# tut1.net
KiCad netlist of a schematic drawn in EAGLE
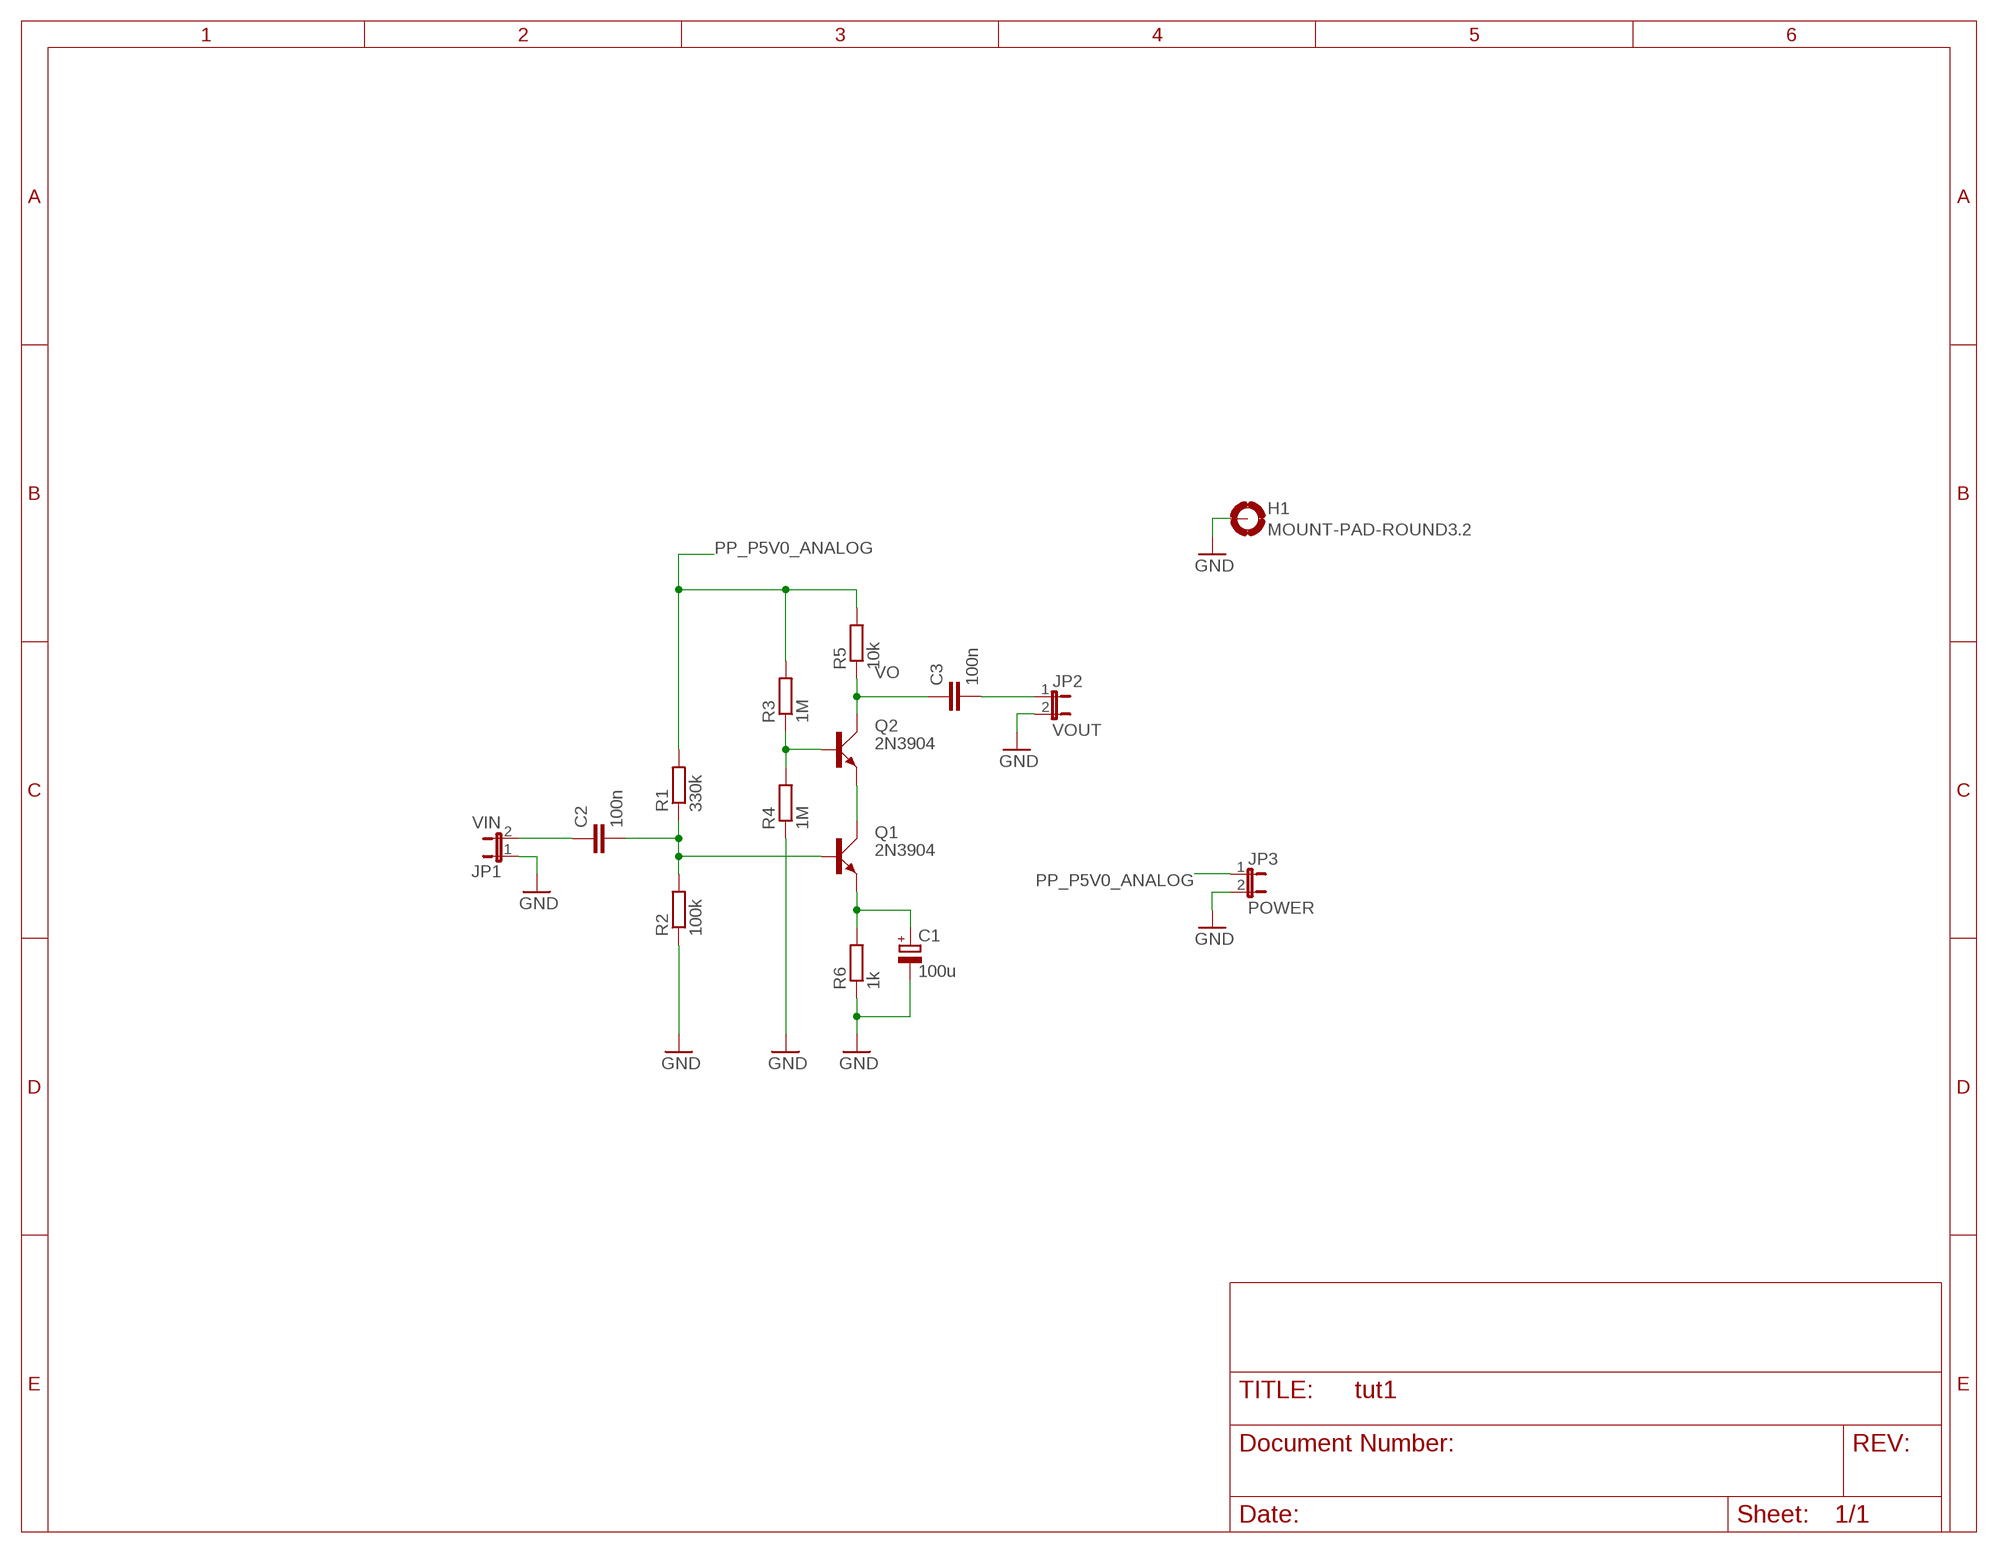
[diagram p0: schematic, sheet 1]

(export (version "E")
  (design (tool "Eeschema 10.0.6"))
  (components
    (comp (ref "C1")
      (value "100u")
      (footprint "eagle-import:E5-10,5")
      (libsource (lib "eagle-import") (part "CPOL-EUE5-10.5"))
    )
    (comp (ref "C2")
      (value "100n")
      (footprint "eagle-import:C050-025X075")
      (libsource (lib "eagle-import") (part "C-EU050-025X075"))
    )
    (comp (ref "C3")
      (value "100n")
      (footprint "eagle-import:C050-025X075")
      (libsource (lib "eagle-import") (part "C-EU050-025X075"))
    )
    (comp (ref "H1")
      (value "MOUNT-PAD-ROUND3.2")
      (footprint "eagle-import:3,2-PAD")
      (libsource (lib "eagle-import") (part "MOUNT-PAD-ROUND3.2"))
    )
    (comp (ref "JP1")
      (value "VIN")
      (footprint "eagle-import:JP1")
      (libsource (lib "eagle-import") (part "JP1E"))
    )
    (comp (ref "JP2")
      (value "VOUT")
      (footprint "eagle-import:JP1")
      (libsource (lib "eagle-import") (part "JP1E"))
    )
    (comp (ref "JP3")
      (value "POWER")
      (footprint "eagle-import:JP1")
      (libsource (lib "eagle-import") (part "JP1E"))
    )
    (comp (ref "Q1")
      (value "2N3904")
      (footprint "eagle-import:TO92D")
      (libsource (lib "eagle-import") (part "2N3904"))
    )
    (comp (ref "Q2")
      (value "2N3904")
      (footprint "eagle-import:TO92D")
      (libsource (lib "eagle-import") (part "2N3904"))
    )
    (comp (ref "R1")
      (value "330k")
      (footprint "eagle-import:0207_10")
      (libsource (lib "eagle-import") (part "R-EU_0207/10"))
    )
    (comp (ref "R2")
      (value "100k")
      (footprint "eagle-import:0207_10")
      (libsource (lib "eagle-import") (part "R-EU_0207/10"))
    )
    (comp (ref "R3")
      (value "1M")
      (footprint "eagle-import:0207_10")
      (libsource (lib "eagle-import") (part "R-EU_0207/10"))
    )
    (comp (ref "R4")
      (value "1M")
      (footprint "eagle-import:0207_10")
      (libsource (lib "eagle-import") (part "R-EU_0207/10"))
    )
    (comp (ref "R5")
      (value "10k")
      (footprint "eagle-import:0207_10")
      (libsource (lib "eagle-import") (part "R-EU_0207/10"))
    )
    (comp (ref "R6")
      (value "1k")
      (footprint "eagle-import:0207_10")
      (libsource (lib "eagle-import") (part "R-EU_0207/10"))
    )
  )
  (nets
    (net (code "1") (name "/PP_P5V0_ANALOG") (class "Default")
      (node (ref "JP3") (pin "1") (pinfunction "1_1") (pintype "passive"))
      (node (ref "R1") (pin "2") (pinfunction "2_2") (pintype "passive"))
      (node (ref "R3") (pin "2") (pinfunction "2_2") (pintype "passive"))
      (node (ref "R5") (pin "2") (pinfunction "2_2") (pintype "passive"))
    )
    (net (code "2") (name "/VO") (class "Default")
      (node (ref "C3") (pin "1") (pinfunction "1_1") (pintype "passive"))
      (node (ref "Q2") (pin "C") (pinfunction "C_C") (pintype "passive"))
      (node (ref "R5") (pin "1") (pinfunction "1_1") (pintype "passive"))
    )
    (net (code "3") (name "GND") (class "Default")
      (node (ref "C1") (pin "-") (pinfunction "-_-") (pintype "passive"))
      (node (ref "H1") (pin "B3,2") (pinfunction "MOUNT_B3,2") (pintype "passive"))
      (node (ref "JP1") (pin "1") (pinfunction "1_1") (pintype "passive"))
      (node (ref "JP2") (pin "2") (pinfunction "2_2") (pintype "passive"))
      (node (ref "JP3") (pin "2") (pinfunction "2_2") (pintype "passive"))
      (node (ref "R2") (pin "1") (pinfunction "1_1") (pintype "passive"))
      (node (ref "R4") (pin "1") (pinfunction "1_1") (pintype "passive"))
      (node (ref "R6") (pin "1") (pinfunction "1_1") (pintype "passive"))
    )
    (net (code "4") (name "Net-(C1-Pad+)") (class "Default")
      (node (ref "C1") (pin "+") (pinfunction "+_+") (pintype "passive"))
      (node (ref "Q1") (pin "E") (pinfunction "E_E") (pintype "passive"))
      (node (ref "R6") (pin "2") (pinfunction "2_2") (pintype "passive"))
    )
    (net (code "5") (name "Net-(C2-Pad1)") (class "Default")
      (node (ref "C2") (pin "1") (pinfunction "1_1") (pintype "passive"))
      (node (ref "JP1") (pin "2") (pinfunction "2_2") (pintype "passive"))
    )
    (net (code "6") (name "Net-(C2-Pad2)") (class "Default")
      (node (ref "C2") (pin "2") (pinfunction "2_2") (pintype "passive"))
      (node (ref "Q1") (pin "B") (pinfunction "B_B") (pintype "passive"))
      (node (ref "R1") (pin "1") (pinfunction "1_1") (pintype "passive"))
      (node (ref "R2") (pin "2") (pinfunction "2_2") (pintype "passive"))
    )
    (net (code "7") (name "Net-(C3-Pad2)") (class "Default")
      (node (ref "C3") (pin "2") (pinfunction "2_2") (pintype "passive"))
      (node (ref "JP2") (pin "1") (pinfunction "1_1") (pintype "passive"))
    )
    (net (code "8") (name "Net-(Q1-PadC)") (class "Default")
      (node (ref "Q1") (pin "C") (pinfunction "C_C") (pintype "passive"))
      (node (ref "Q2") (pin "E") (pinfunction "E_E") (pintype "passive"))
    )
    (net (code "9") (name "Net-(Q2-PadB)") (class "Default")
      (node (ref "Q2") (pin "B") (pinfunction "B_B") (pintype "passive"))
      (node (ref "R3") (pin "1") (pinfunction "1_1") (pintype "passive"))
      (node (ref "R4") (pin "2") (pinfunction "2_2") (pintype "passive"))
    )
  )
)
